# pipe_corner_noled_schematic.net
KiCad netlist of a schematic drawn in Altium Designer
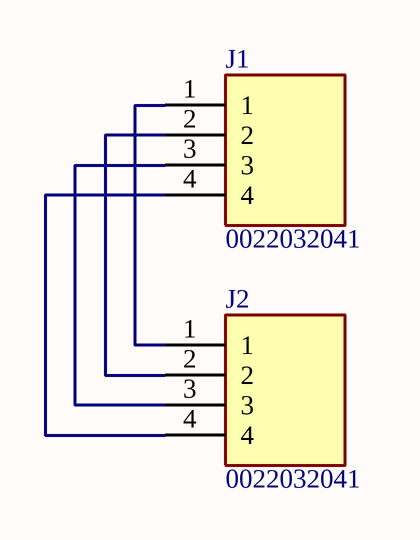
[diagram p0: pipe_corner_noled_schematic.SchDoc]

(export (version "E")
  (design (tool "Eeschema 10.0.6"))
  (components
    (comp (ref "J1")
      (value "0022032041")
      (footprint "SamacSys:HDRV4W87P0X254_1X4_991X236X1155P")
      (description "Connector")
      (libsource (lib "*") (part "0022032041"))
    )
    (comp (ref "J2")
      (value "0022032041")
      (footprint "SamacSys:HDRV4W87P0X254_1X4_991X236X1155P")
      (description "Connector")
      (libsource (lib "*") (part "0022032041"))
    )
  )
  (nets
    (net (code "1") (name "Net-(J1-Pad1)") (class "Default")
      (node (ref "J1") (pin "1") (pinfunction "1_1") (pintype "passive"))
      (node (ref "J2") (pin "1") (pinfunction "1_1") (pintype "passive"))
    )
    (net (code "2") (name "Net-(J1-Pad2)") (class "Default")
      (node (ref "J1") (pin "2") (pinfunction "2_2") (pintype "passive"))
      (node (ref "J2") (pin "2") (pinfunction "2_2") (pintype "passive"))
    )
    (net (code "3") (name "Net-(J1-Pad3)") (class "Default")
      (node (ref "J1") (pin "3") (pinfunction "3_3") (pintype "passive"))
      (node (ref "J2") (pin "3") (pinfunction "3_3") (pintype "passive"))
    )
    (net (code "4") (name "Net-(J1-Pad4)") (class "Default")
      (node (ref "J1") (pin "4") (pinfunction "4_4") (pintype "passive"))
      (node (ref "J2") (pin "4") (pinfunction "4_4") (pintype "passive"))
    )
  )
)
